# clock2_v1.net
KiCad netlist of a schematic drawn in EAGLE
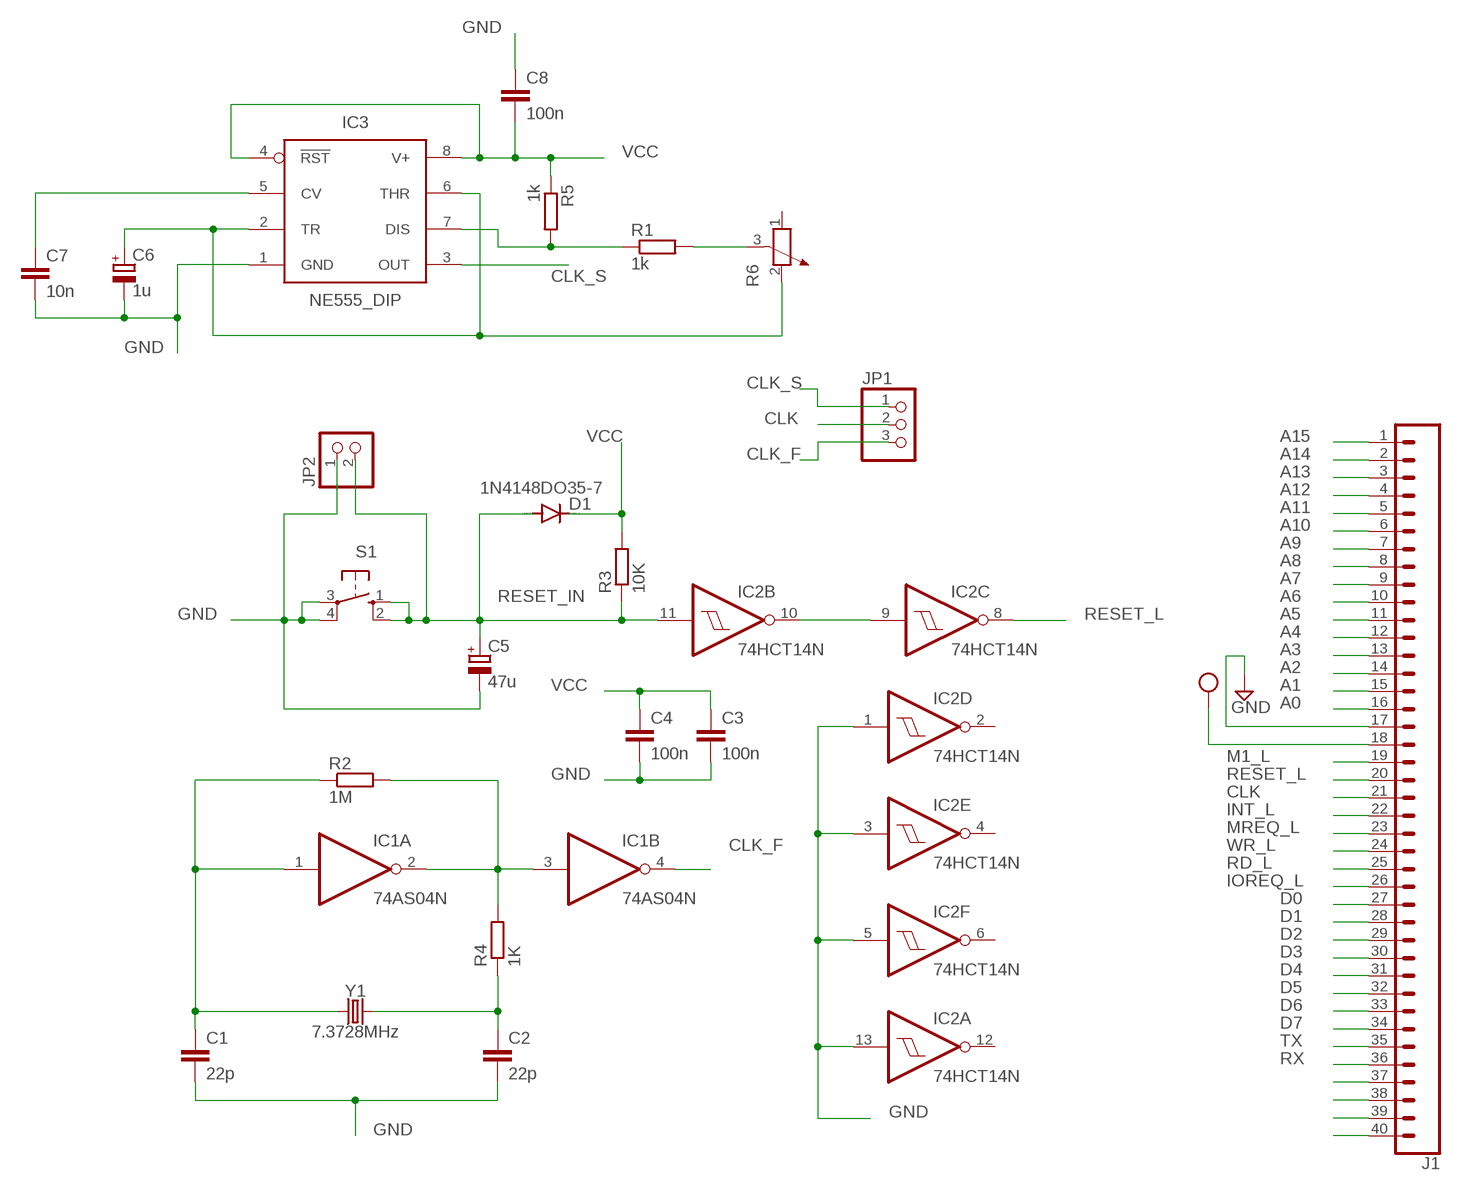
[diagram p0: schematic, sheet 1]

(export (version "E")
  (design (tool "Eeschema 10.0.6"))
  (components
    (comp (ref "C1")
      (value "22p")
      (footprint "eagle-import:C025-024X044")
      (libsource (lib "eagle-import") (part "C-EU025-024X044"))
    )
    (comp (ref "C2")
      (value "22p")
      (footprint "eagle-import:C025-024X044")
      (libsource (lib "eagle-import") (part "C-EU025-024X044"))
    )
    (comp (ref "C3")
      (value "100n")
      (footprint "eagle-import:C025-024X044")
      (libsource (lib "eagle-import") (part "C-EU025-024X044"))
    )
    (comp (ref "C4")
      (value "100n")
      (footprint "eagle-import:C025-024X044")
      (libsource (lib "eagle-import") (part "C-EU025-024X044"))
    )
    (comp (ref "C5")
      (value "47u")
      (footprint "eagle-import:E2,5-5")
      (libsource (lib "eagle-import") (part "CPOL-EUE2.5-5"))
    )
    (comp (ref "C6")
      (value "1u")
      (footprint "eagle-import:E2,5-5")
      (libsource (lib "eagle-import") (part "CPOL-EUE2.5-5"))
    )
    (comp (ref "C7")
      (value "10n")
      (footprint "eagle-import:C050-025X075")
      (libsource (lib "eagle-import") (part "C-EU050-025X075"))
    )
    (comp (ref "C8")
      (value "100n")
      (footprint "eagle-import:C050-025X075")
      (libsource (lib "eagle-import") (part "C-EU050-025X075"))
    )
    (comp (ref "D1")
      (value "1N4148DO35-7")
      (footprint "eagle-import:DO35-7")
      (libsource (lib "eagle-import") (part "1N4148DO35-7"))
    )
    (comp (ref "IC1")
      (value "74AS04N")
      (footprint "eagle-import:DIL14")
      (libsource (lib "eagle-import") (part "7404NAS"))
    )
    (comp (ref "IC2")
      (value "74HCT14N")
      (footprint "eagle-import:DIL14")
      (libsource (lib "eagle-import") (part "7414NHCT"))
    )
    (comp (ref "IC3")
      (value "NE555_DIP")
      (footprint "eagle-import:DIP826W53P254L959H508Q8B")
      (fields (field (name "MANUFACTURER") "Texas Instruments ") (field (name "MPN") "NE555P "))
      (libsource (lib "eagle-import") (part "555_DIPNE"))
    )
    (comp (ref "J1")
      (value "CONN_40OFFSET")
      (footprint "eagle-import:1X40_OFFSET")
      (libsource (lib "eagle-import") (part "CONN_40OFFSET"))
    )
    (comp (ref "JP1")
      (value "PINHD-1X3")
      (footprint "eagle-import:1X03")
      (libsource (lib "eagle-import") (part "PINHD-1X3"))
    )
    (comp (ref "JP2")
      (value "PINHD-1X2")
      (footprint "eagle-import:1X02")
      (libsource (lib "eagle-import") (part "PINHD-1X2"))
    )
    (comp (ref "R1")
      (value "1k")
      (footprint "eagle-import:0207_7")
      (libsource (lib "eagle-import") (part "R-EU_0207/7"))
    )
    (comp (ref "R2")
      (value "1M")
      (footprint "eagle-import:0204_5")
      (libsource (lib "eagle-import") (part "R-EU_0204/5"))
    )
    (comp (ref "R3")
      (value "10K")
      (footprint "eagle-import:0207_7")
      (libsource (lib "eagle-import") (part "R-EU_0207/7"))
    )
    (comp (ref "R4")
      (value "1K")
      (footprint "eagle-import:0204_5")
      (libsource (lib "eagle-import") (part "R-EU_0204/5"))
    )
    (comp (ref "R5")
      (value "1k")
      (footprint "eagle-import:0207_7")
      (libsource (lib "eagle-import") (part "R-EU_0207/7"))
    )
    (comp (ref "R6")
      (value "POTENTIOMETER_PT-10S")
      (footprint "eagle-import:PT-10S")
      (libsource (lib "eagle-import") (part "POTENTIOMETER_PT-10S"))
    )
    (comp (ref "S1")
      (value "10-XX")
      (footprint "eagle-import:B3F-10XX")
      (fields (field (name "MPN") "B3F-1000"))
      (libsource (lib "eagle-import") (part "10-XX"))
    )
    (comp (ref "Y1")
      (value "7.3728MHz")
      (footprint "eagle-import:HC49U")
      (libsource (lib "eagle-import") (part "CRYSTALPTH-HC49UV"))
    )
  )
  (nets
    (net (code "1") (name "/A0") (class "Default")
      (node (ref "J1") (pin "16") (pinfunction "16_16") (pintype "passive"))
    )
    (net (code "2") (name "/A1") (class "Default")
      (node (ref "J1") (pin "15") (pinfunction "15_15") (pintype "passive"))
    )
    (net (code "3") (name "/A2") (class "Default")
      (node (ref "J1") (pin "14") (pinfunction "14_14") (pintype "passive"))
    )
    (net (code "4") (name "/A3") (class "Default")
      (node (ref "J1") (pin "13") (pinfunction "13_13") (pintype "passive"))
    )
    (net (code "5") (name "/A4") (class "Default")
      (node (ref "J1") (pin "12") (pinfunction "12_12") (pintype "passive"))
    )
    (net (code "6") (name "/A5") (class "Default")
      (node (ref "J1") (pin "11") (pinfunction "11_11") (pintype "passive"))
    )
    (net (code "7") (name "/A6") (class "Default")
      (node (ref "J1") (pin "10") (pinfunction "10_10") (pintype "passive"))
    )
    (net (code "8") (name "/A7") (class "Default")
      (node (ref "J1") (pin "9") (pinfunction "9_9") (pintype "passive"))
    )
    (net (code "9") (name "/A8") (class "Default")
      (node (ref "J1") (pin "8") (pinfunction "8_8") (pintype "passive"))
    )
    (net (code "10") (name "/A9") (class "Default")
      (node (ref "J1") (pin "7") (pinfunction "7_7") (pintype "passive"))
    )
    (net (code "11") (name "/A10") (class "Default")
      (node (ref "J1") (pin "6") (pinfunction "6_6") (pintype "passive"))
    )
    (net (code "12") (name "/A11") (class "Default")
      (node (ref "J1") (pin "5") (pinfunction "5_5") (pintype "passive"))
    )
    (net (code "13") (name "/A12") (class "Default")
      (node (ref "J1") (pin "4") (pinfunction "4_4") (pintype "passive"))
    )
    (net (code "14") (name "/A13") (class "Default")
      (node (ref "J1") (pin "3") (pinfunction "3_3") (pintype "passive"))
    )
    (net (code "15") (name "/A14") (class "Default")
      (node (ref "J1") (pin "2") (pinfunction "2_2") (pintype "passive"))
    )
    (net (code "16") (name "/A15") (class "Default")
      (node (ref "J1") (pin "1") (pinfunction "1_1") (pintype "passive"))
    )
    (net (code "17") (name "/CLK") (class "Default")
      (node (ref "J1") (pin "21") (pinfunction "21_21") (pintype "passive"))
      (node (ref "JP1") (pin "2") (pinfunction "2_2") (pintype "passive"))
    )
    (net (code "18") (name "/CLK_F") (class "Default")
      (node (ref "IC1") (pin "4") (pinfunction "O_4") (pintype "output"))
      (node (ref "JP1") (pin "3") (pinfunction "3_3") (pintype "passive"))
    )
    (net (code "19") (name "/CLK_S") (class "Default")
      (node (ref "IC3") (pin "3") (pinfunction "OUT_3") (pintype "output"))
      (node (ref "JP1") (pin "1") (pinfunction "1_1") (pintype "passive"))
    )
    (net (code "20") (name "/D0") (class "Default")
      (node (ref "J1") (pin "27") (pinfunction "27_27") (pintype "passive"))
    )
    (net (code "21") (name "/D1") (class "Default")
      (node (ref "J1") (pin "28") (pinfunction "28_28") (pintype "passive"))
    )
    (net (code "22") (name "/D2") (class "Default")
      (node (ref "J1") (pin "29") (pinfunction "29_29") (pintype "passive"))
    )
    (net (code "23") (name "/D3") (class "Default")
      (node (ref "J1") (pin "30") (pinfunction "30_30") (pintype "passive"))
    )
    (net (code "24") (name "/D4") (class "Default")
      (node (ref "J1") (pin "31") (pinfunction "31_31") (pintype "passive"))
    )
    (net (code "25") (name "/D5") (class "Default")
      (node (ref "J1") (pin "32") (pinfunction "32_32") (pintype "passive"))
    )
    (net (code "26") (name "/D6") (class "Default")
      (node (ref "J1") (pin "33") (pinfunction "33_33") (pintype "passive"))
    )
    (net (code "27") (name "/D7") (class "Default")
      (node (ref "J1") (pin "34") (pinfunction "34_34") (pintype "passive"))
    )
    (net (code "28") (name "/INT_L") (class "Default")
      (node (ref "J1") (pin "22") (pinfunction "22_22") (pintype "passive"))
    )
    (net (code "29") (name "/IOREQ_L") (class "Default")
      (node (ref "J1") (pin "26") (pinfunction "26_26") (pintype "passive"))
    )
    (net (code "30") (name "/M1_L") (class "Default")
      (node (ref "J1") (pin "19") (pinfunction "19_19") (pintype "passive"))
    )
    (net (code "31") (name "/MREQ_L") (class "Default")
      (node (ref "J1") (pin "23") (pinfunction "23_23") (pintype "passive"))
    )
    (net (code "32") (name "/RD_L") (class "Default")
      (node (ref "J1") (pin "25") (pinfunction "25_25") (pintype "passive"))
    )
    (net (code "33") (name "/RESET_IN") (class "Default")
      (node (ref "C5") (pin "+") (pinfunction "+_+") (pintype "passive"))
      (node (ref "D1") (pin "A") (pinfunction "A_A") (pintype "passive"))
      (node (ref "IC2") (pin "11") (pinfunction "I_11") (pintype "input"))
      (node (ref "JP2") (pin "2") (pinfunction "2_2") (pintype "passive"))
      (node (ref "R3") (pin "1") (pinfunction "1_1") (pintype "passive"))
      (node (ref "S1") (pin "1") (pinfunction "S_1") (pintype "passive"))
      (node (ref "S1") (pin "2") (pinfunction "S1_2") (pintype "passive"))
    )
    (net (code "34") (name "/RESET_L") (class "Default")
      (node (ref "IC2") (pin "8") (pinfunction "O_8") (pintype "output"))
      (node (ref "J1") (pin "20") (pinfunction "20_20") (pintype "passive"))
    )
    (net (code "35") (name "/RX") (class "Default")
      (node (ref "J1") (pin "36") (pinfunction "36_36") (pintype "passive"))
    )
    (net (code "36") (name "/TX") (class "Default")
      (node (ref "J1") (pin "35") (pinfunction "35_35") (pintype "passive"))
    )
    (net (code "37") (name "/WR_L") (class "Default")
      (node (ref "J1") (pin "24") (pinfunction "24_24") (pintype "passive"))
    )
    (net (code "38") (name "GND") (class "Default")
      (node (ref "C1") (pin "2") (pinfunction "2_2") (pintype "passive"))
      (node (ref "C2") (pin "2") (pinfunction "2_2") (pintype "passive"))
      (node (ref "C3") (pin "2") (pinfunction "2_2") (pintype "passive"))
      (node (ref "C4") (pin "2") (pinfunction "2_2") (pintype "passive"))
      (node (ref "C5") (pin "-") (pinfunction "-_-") (pintype "passive"))
      (node (ref "C6") (pin "-") (pinfunction "-_-") (pintype "passive"))
      (node (ref "C7") (pin "2") (pinfunction "2_2") (pintype "passive"))
      (node (ref "C8") (pin "1") (pinfunction "1_1") (pintype "passive"))
      (node (ref "IC2") (pin "1") (pinfunction "I_1") (pintype "input"))
      (node (ref "IC2") (pin "13") (pinfunction "I_13") (pintype "input"))
      (node (ref "IC2") (pin "3") (pinfunction "I_3") (pintype "input"))
      (node (ref "IC2") (pin "5") (pinfunction "I_5") (pintype "input"))
      (node (ref "IC3") (pin "1") (pinfunction "GND_1") (pintype "power_in"))
      (node (ref "J1") (pin "17") (pinfunction "17_17") (pintype "passive"))
      (node (ref "JP2") (pin "1") (pinfunction "1_1") (pintype "passive"))
      (node (ref "S1") (pin "3") (pinfunction "P_3") (pintype "passive"))
      (node (ref "S1") (pin "4") (pinfunction "P1_4") (pintype "passive"))
    )
    (net (code "39") (name "Net-(C2-Pad1)") (class "Default")
      (node (ref "C2") (pin "1") (pinfunction "1_1") (pintype "passive"))
      (node (ref "R4") (pin "1") (pinfunction "1_1") (pintype "passive"))
      (node (ref "Y1") (pin "2") (pinfunction "2_2") (pintype "passive"))
    )
    (net (code "40") (name "Net-(IC1A-I)") (class "Default")
      (node (ref "C1") (pin "1") (pinfunction "1_1") (pintype "passive"))
      (node (ref "IC1") (pin "1") (pinfunction "I_1") (pintype "input"))
      (node (ref "R2") (pin "1") (pinfunction "1_1") (pintype "passive"))
      (node (ref "Y1") (pin "1") (pinfunction "1_1") (pintype "passive"))
    )
    (net (code "41") (name "Net-(IC1A-O)") (class "Default")
      (node (ref "IC1") (pin "2") (pinfunction "O_2") (pintype "output"))
      (node (ref "IC1") (pin "3") (pinfunction "I_3") (pintype "input"))
      (node (ref "R2") (pin "2") (pinfunction "2_2") (pintype "passive"))
      (node (ref "R4") (pin "2") (pinfunction "2_2") (pintype "passive"))
    )
    (net (code "42") (name "Net-(IC2B-O)") (class "Default")
      (node (ref "IC2") (pin "10") (pinfunction "O_10") (pintype "output"))
      (node (ref "IC2") (pin "9") (pinfunction "I_9") (pintype "input"))
    )
    (net (code "43") (name "Net-(IC3-CV)") (class "Default")
      (node (ref "C7") (pin "1") (pinfunction "1_1") (pintype "passive"))
      (node (ref "IC3") (pin "5") (pinfunction "CV_5") (pintype "input"))
    )
    (net (code "44") (name "Net-(IC3-DIS)") (class "Default")
      (node (ref "IC3") (pin "7") (pinfunction "DIS_7") (pintype "input"))
      (node (ref "R1") (pin "1") (pinfunction "1_1") (pintype "passive"))
      (node (ref "R5") (pin "2") (pinfunction "2_2") (pintype "passive"))
    )
    (net (code "45") (name "Net-(IC3-THR)") (class "Default")
      (node (ref "C6") (pin "+") (pinfunction "+_+") (pintype "passive"))
      (node (ref "IC3") (pin "2") (pinfunction "TR_2") (pintype "input"))
      (node (ref "IC3") (pin "6") (pinfunction "THR_6") (pintype "input"))
      (node (ref "R6") (pin "2") (pinfunction "2_2") (pintype "passive"))
    )
    (net (code "46") (name "Net-(R1-Pad2)") (class "Default")
      (node (ref "R1") (pin "2") (pinfunction "2_2") (pintype "passive"))
      (node (ref "R6") (pin "3") (pinfunction "3_3") (pintype "passive"))
    )
    (net (code "47") (name "VCC") (class "Default")
      (node (ref "C3") (pin "1") (pinfunction "1_1") (pintype "passive"))
      (node (ref "C4") (pin "1") (pinfunction "1_1") (pintype "passive"))
      (node (ref "C8") (pin "2") (pinfunction "2_2") (pintype "passive"))
      (node (ref "D1") (pin "C") (pinfunction "C_C") (pintype "passive"))
      (node (ref "IC3") (pin "4") (pinfunction "~{RST}_4") (pintype "input"))
      (node (ref "IC3") (pin "8") (pinfunction "V+_8") (pintype "power_in"))
      (node (ref "J1") (pin "18") (pinfunction "18_18") (pintype "passive"))
      (node (ref "R3") (pin "2") (pinfunction "2_2") (pintype "passive"))
      (node (ref "R5") (pin "1") (pinfunction "1_1") (pintype "passive"))
    )
    (net (code "48") (name "unconnected-(IC2A-O-Pad12)") (class "Default")
      (node (ref "IC2") (pin "12") (pinfunction "O_12") (pintype "output"))
    )
    (net (code "49") (name "unconnected-(IC2D-O-Pad2)") (class "Default")
      (node (ref "IC2") (pin "2") (pinfunction "O_2") (pintype "output"))
    )
    (net (code "50") (name "unconnected-(IC2E-O-Pad4)") (class "Default")
      (node (ref "IC2") (pin "4") (pinfunction "O_4") (pintype "output"))
    )
    (net (code "51") (name "unconnected-(IC2F-O-Pad6)") (class "Default")
      (node (ref "IC2") (pin "6") (pinfunction "O_6") (pintype "output"))
    )
    (net (code "52") (name "unconnected-(J1-Pad37)") (class "Default")
      (node (ref "J1") (pin "37") (pinfunction "37_37") (pintype "passive"))
    )
    (net (code "53") (name "unconnected-(J1-Pad38)") (class "Default")
      (node (ref "J1") (pin "38") (pinfunction "38_38") (pintype "passive"))
    )
    (net (code "54") (name "unconnected-(J1-Pad39)") (class "Default")
      (node (ref "J1") (pin "39") (pinfunction "39_39") (pintype "passive"))
    )
    (net (code "55") (name "unconnected-(J1-Pad40)") (class "Default")
      (node (ref "J1") (pin "40") (pinfunction "40_40") (pintype "passive"))
    )
    (net (code "56") (name "unconnected-(R6-Pad1)") (class "Default")
      (node (ref "R6") (pin "1") (pinfunction "1_1") (pintype "passive"))
    )
  )
)
